# untitled.net
KiCad netlist of a schematic drawn in EAGLE
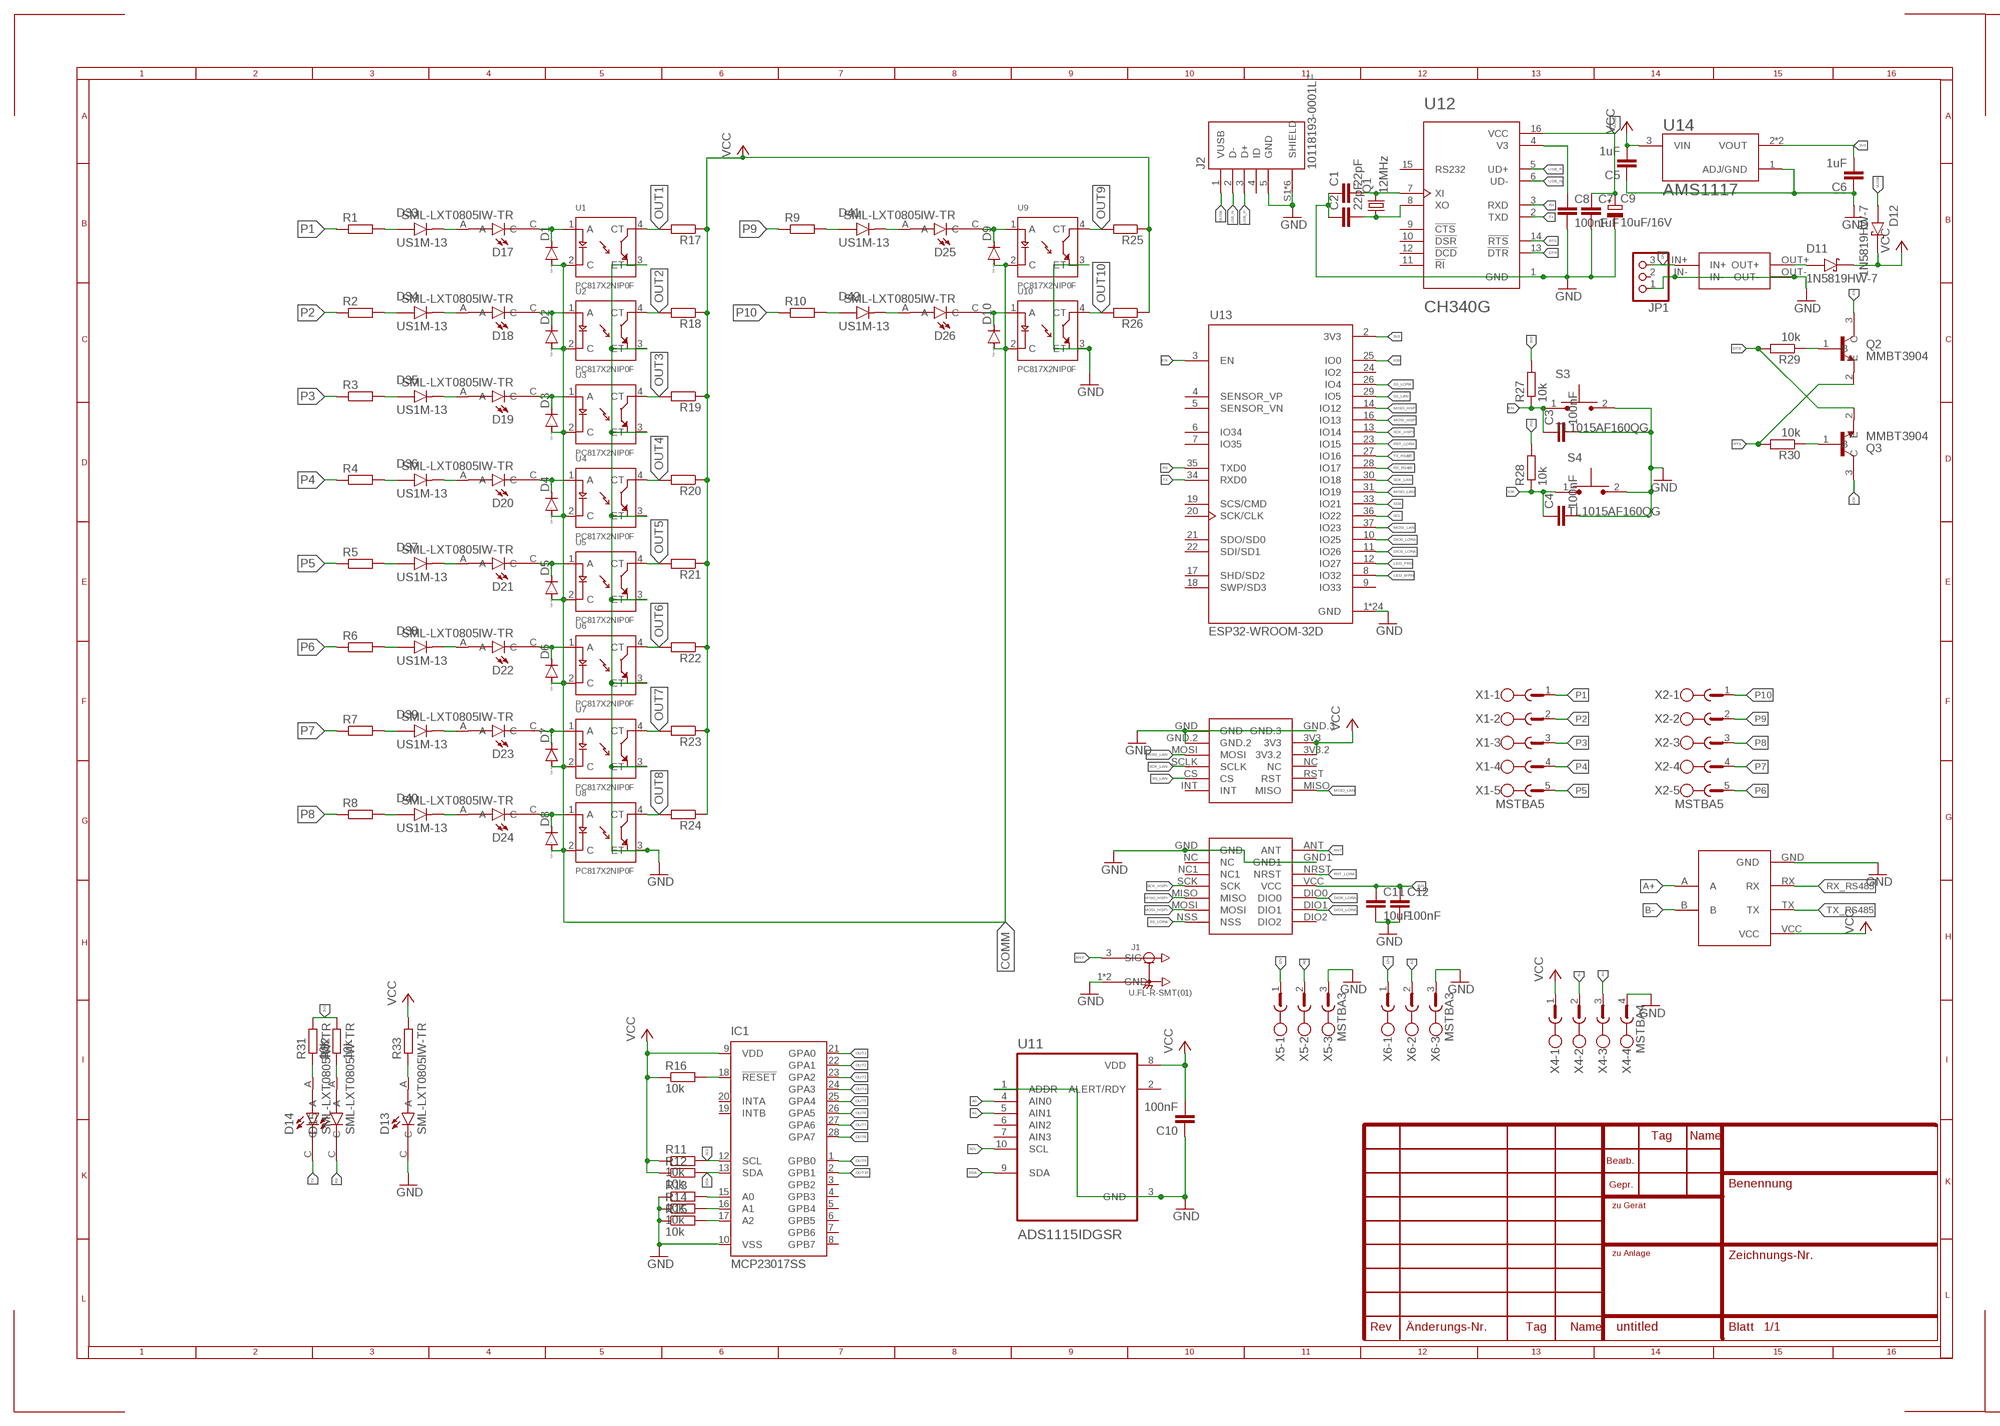
[diagram p0: schematic, sheet 1, part 1 of 2]
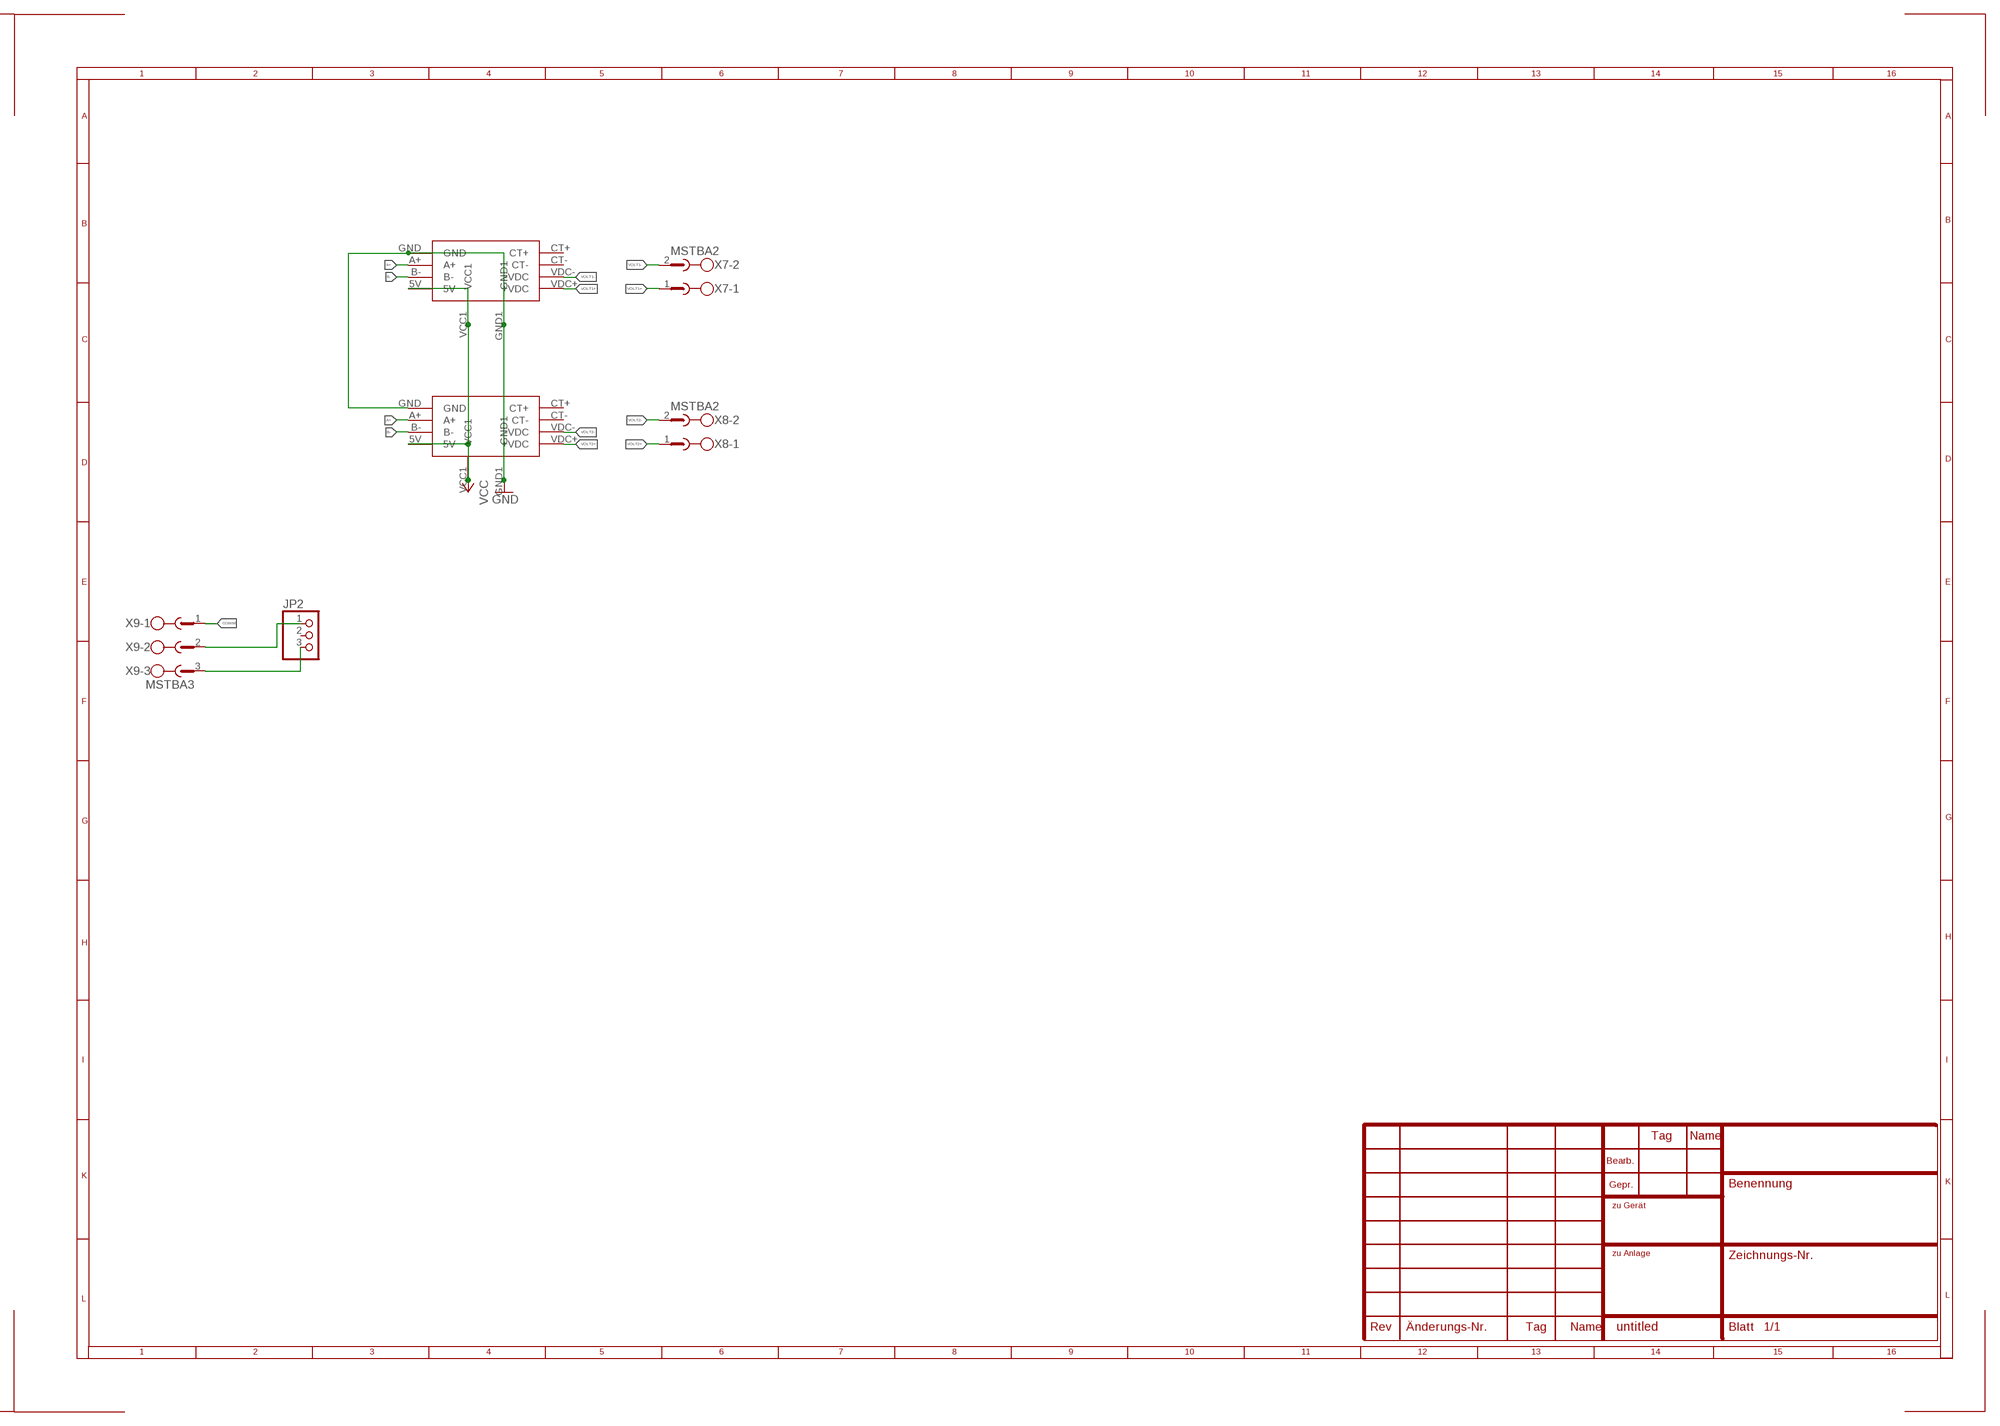
[diagram p1: schematic, sheet 1, part 2 of 2]

(export (version "E")
  (design (tool "Eeschema 10.0.6"))
  (components
    (comp (ref "C1")
      (value "22pF")
      (footprint "eagle-import:C0805K")
      (libsource (lib "eagle-import") (part "C-EUC0805K"))
    )
    (comp (ref "C2")
      (value "22pF")
      (footprint "eagle-import:C0805K")
      (libsource (lib "eagle-import") (part "C-EUC0805K"))
    )
    (comp (ref "C3")
      (value "100nF")
      (footprint "eagle-import:C0805K")
      (libsource (lib "eagle-import") (part "C-EUC0805K"))
    )
    (comp (ref "C4")
      (value "100nF")
      (footprint "eagle-import:C0805K")
      (libsource (lib "eagle-import") (part "C-EUC0805K"))
    )
    (comp (ref "C5")
      (value "1uF")
      (footprint "eagle-import:C0805K")
      (libsource (lib "eagle-import") (part "C-EUC0805K"))
    )
    (comp (ref "C6")
      (value "1uF")
      (footprint "eagle-import:C0805K")
      (libsource (lib "eagle-import") (part "C-EUC0805K"))
    )
    (comp (ref "C7")
      (value "1uF")
      (footprint "eagle-import:C0805K")
      (libsource (lib "eagle-import") (part "C-EUC0805K"))
    )
    (comp (ref "C8")
      (value "100nF")
      (footprint "eagle-import:C0805K")
      (libsource (lib "eagle-import") (part "C-EUC0805K"))
    )
    (comp (ref "C9")
      (value "10uF/16V")
      (footprint "eagle-import:153CLV-0505")
      (libsource (lib "eagle-import") (part "CPOL-EU153CLV-0505"))
    )
    (comp (ref "C10")
      (value "100nF")
      (footprint "eagle-import:C0805K")
      (libsource (lib "eagle-import") (part "C-EUC0805K"))
    )
    (comp (ref "C11")
      (value "10uF")
      (footprint "eagle-import:C0805K")
      (libsource (lib "eagle-import") (part "C-EUC0805K"))
    )
    (comp (ref "C12")
      (value "100nF")
      (footprint "eagle-import:C0805K")
      (libsource (lib "eagle-import") (part "C-EUC0805K"))
    )
    (comp (ref "D1")
      (value "DIODE-SOD123")
      (footprint "eagle-import:SOD123")
      (libsource (lib "eagle-import") (part "DIODE-SOD123"))
    )
    (comp (ref "D2")
      (value "DIODE-SOD123")
      (footprint "eagle-import:SOD123")
      (libsource (lib "eagle-import") (part "DIODE-SOD123"))
    )
    (comp (ref "D3")
      (value "DIODE-SOD123")
      (footprint "eagle-import:SOD123")
      (libsource (lib "eagle-import") (part "DIODE-SOD123"))
    )
    (comp (ref "D4")
      (value "DIODE-SOD123")
      (footprint "eagle-import:SOD123")
      (libsource (lib "eagle-import") (part "DIODE-SOD123"))
    )
    (comp (ref "D5")
      (value "DIODE-SOD123")
      (footprint "eagle-import:SOD123")
      (libsource (lib "eagle-import") (part "DIODE-SOD123"))
    )
    (comp (ref "D6")
      (value "DIODE-SOD123")
      (footprint "eagle-import:SOD123")
      (libsource (lib "eagle-import") (part "DIODE-SOD123"))
    )
    (comp (ref "D7")
      (value "DIODE-SOD123")
      (footprint "eagle-import:SOD123")
      (libsource (lib "eagle-import") (part "DIODE-SOD123"))
    )
    (comp (ref "D8")
      (value "DIODE-SOD123")
      (footprint "eagle-import:SOD123")
      (libsource (lib "eagle-import") (part "DIODE-SOD123"))
    )
    (comp (ref "D9")
      (value "DIODE-SOD123")
      (footprint "eagle-import:SOD123")
      (libsource (lib "eagle-import") (part "DIODE-SOD123"))
    )
    (comp (ref "D10")
      (value "DIODE-SOD123")
      (footprint "eagle-import:SOD123")
      (libsource (lib "eagle-import") (part "DIODE-SOD123"))
    )
    (comp (ref "D11")
      (value "1N5819HW-7")
      (footprint "eagle-import:SOD3715X145N")
      (fields (field (name "MF") "Diodes Inc."))
      (libsource (lib "eagle-import") (part "1N5819HW-7"))
    )
    (comp (ref "D12")
      (value "1N5819HW-7")
      (footprint "eagle-import:SOD3715X145N")
      (fields (field (name "MF") "Diodes Inc."))
      (libsource (lib "eagle-import") (part "1N5819HW-7"))
    )
    (comp (ref "D13")
      (value "SML-LXT0805IW-TR")
      (footprint "eagle-import:LEDC2012X120N")
      (fields (field (name "MF") "Lumex Opto/Components"))
      (libsource (lib "eagle-import") (part "SML-LXT0805IW-TR"))
    )
    (comp (ref "D14")
      (value "SML-LXT0805IW-TR")
      (footprint "eagle-import:LEDC2012X120N")
      (fields (field (name "MF") "Lumex Opto/Components"))
      (libsource (lib "eagle-import") (part "SML-LXT0805IW-TR"))
    )
    (comp (ref "D15")
      (value "SML-LXT0805IW-TR")
      (footprint "eagle-import:LEDC2012X120N")
      (fields (field (name "MF") "Lumex Opto/Components"))
      (libsource (lib "eagle-import") (part "SML-LXT0805IW-TR"))
    )
    (comp (ref "D17")
      (value "SML-LXT0805IW-TR")
      (footprint "eagle-import:LEDC2012X120N")
      (fields (field (name "MF") "Lumex Opto/Components"))
      (libsource (lib "eagle-import") (part "SML-LXT0805IW-TR"))
    )
    (comp (ref "D18")
      (value "SML-LXT0805IW-TR")
      (footprint "eagle-import:LEDC2012X120N")
      (fields (field (name "MF") "Lumex Opto/Components"))
      (libsource (lib "eagle-import") (part "SML-LXT0805IW-TR"))
    )
    (comp (ref "D19")
      (value "SML-LXT0805IW-TR")
      (footprint "eagle-import:LEDC2012X120N")
      (fields (field (name "MF") "Lumex Opto/Components"))
      (libsource (lib "eagle-import") (part "SML-LXT0805IW-TR"))
    )
    (comp (ref "D20")
      (value "SML-LXT0805IW-TR")
      (footprint "eagle-import:LEDC2012X120N")
      (fields (field (name "MF") "Lumex Opto/Components"))
      (libsource (lib "eagle-import") (part "SML-LXT0805IW-TR"))
    )
    (comp (ref "D21")
      (value "SML-LXT0805IW-TR")
      (footprint "eagle-import:LEDC2012X120N")
      (fields (field (name "MF") "Lumex Opto/Components"))
      (libsource (lib "eagle-import") (part "SML-LXT0805IW-TR"))
    )
    (comp (ref "D22")
      (value "SML-LXT0805IW-TR")
      (footprint "eagle-import:LEDC2012X120N")
      (fields (field (name "MF") "Lumex Opto/Components"))
      (libsource (lib "eagle-import") (part "SML-LXT0805IW-TR"))
    )
    (comp (ref "D23")
      (value "SML-LXT0805IW-TR")
      (footprint "eagle-import:LEDC2012X120N")
      (fields (field (name "MF") "Lumex Opto/Components"))
      (libsource (lib "eagle-import") (part "SML-LXT0805IW-TR"))
    )
    (comp (ref "D24")
      (value "SML-LXT0805IW-TR")
      (footprint "eagle-import:LEDC2012X120N")
      (fields (field (name "MF") "Lumex Opto/Components"))
      (libsource (lib "eagle-import") (part "SML-LXT0805IW-TR"))
    )
    (comp (ref "D25")
      (value "SML-LXT0805IW-TR")
      (footprint "eagle-import:LEDC2012X120N")
      (fields (field (name "MF") "Lumex Opto/Components"))
      (libsource (lib "eagle-import") (part "SML-LXT0805IW-TR"))
    )
    (comp (ref "D26")
      (value "SML-LXT0805IW-TR")
      (footprint "eagle-import:LEDC2012X120N")
      (fields (field (name "MF") "Lumex Opto/Components"))
      (libsource (lib "eagle-import") (part "SML-LXT0805IW-TR"))
    )
    (comp (ref "D33")
      (value "US1M-13")
      (footprint "eagle-import:DIOM5226X240N")
      (fields (field (name "MF") "Diodes Incorporated"))
      (libsource (lib "eagle-import") (part "US1M-13"))
    )
    (comp (ref "D34")
      (value "US1M-13")
      (footprint "eagle-import:DIOM5226X240N")
      (fields (field (name "MF") "Diodes Incorporated"))
      (libsource (lib "eagle-import") (part "US1M-13"))
    )
    (comp (ref "D35")
      (value "US1M-13")
      (footprint "eagle-import:DIOM5226X240N")
      (fields (field (name "MF") "Diodes Incorporated"))
      (libsource (lib "eagle-import") (part "US1M-13"))
    )
    (comp (ref "D36")
      (value "US1M-13")
      (footprint "eagle-import:DIOM5226X240N")
      (fields (field (name "MF") "Diodes Incorporated"))
      (libsource (lib "eagle-import") (part "US1M-13"))
    )
    (comp (ref "D37")
      (value "US1M-13")
      (footprint "eagle-import:DIOM5226X240N")
      (fields (field (name "MF") "Diodes Incorporated"))
      (libsource (lib "eagle-import") (part "US1M-13"))
    )
    (comp (ref "D38")
      (value "US1M-13")
      (footprint "eagle-import:DIOM5226X240N")
      (fields (field (name "MF") "Diodes Incorporated"))
      (libsource (lib "eagle-import") (part "US1M-13"))
    )
    (comp (ref "D39")
      (value "US1M-13")
      (footprint "eagle-import:DIOM5226X240N")
      (fields (field (name "MF") "Diodes Incorporated"))
      (libsource (lib "eagle-import") (part "US1M-13"))
    )
    (comp (ref "D40")
      (value "US1M-13")
      (footprint "eagle-import:DIOM5226X240N")
      (fields (field (name "MF") "Diodes Incorporated"))
      (libsource (lib "eagle-import") (part "US1M-13"))
    )
    (comp (ref "D41")
      (value "US1M-13")
      (footprint "eagle-import:DIOM5226X240N")
      (fields (field (name "MF") "Diodes Incorporated"))
      (libsource (lib "eagle-import") (part "US1M-13"))
    )
    (comp (ref "D42")
      (value "US1M-13")
      (footprint "eagle-import:DIOM5226X240N")
      (fields (field (name "MF") "Diodes Incorporated"))
      (libsource (lib "eagle-import") (part "US1M-13"))
    )
    (comp (ref "IC1")
      (value "MCP23017SS")
      (footprint "eagle-import:SSOP28")
      (fields (field (name "MF") "MICROCHIP") (field (name "MPN") "MCP23017-E/SS"))
      (libsource (lib "eagle-import") (part "MCP23017SS"))
    )
    (comp (ref "J1")
      (value "U.FL-R-SMT(01)")
      (footprint "eagle-import:HRS_U.FL-R-SMT(01)")
      (fields (field (name "MF") "Hirose"))
      (libsource (lib "eagle-import") (part "U.FL-R-SMT(01)"))
    )
    (comp (ref "J2")
      (value "10118193-0001LF")
      (footprint "eagle-import:FCI_10118193-0001LF")
      (fields (field (name "MF") "FCI"))
      (libsource (lib "eagle-import") (part "10118193-0001LF"))
    )
    (comp (ref "JP1")
      (value "PINHD-1X3CB")
      (footprint "eagle-import:1X03-CLEANBIG")
      (libsource (lib "eagle-import") (part "PINHD-1X3CB"))
    )
    (comp (ref "JP2")
      (value "PINHD-1X3CB")
      (footprint "eagle-import:1X03-CLEANBIG")
      (libsource (lib "eagle-import") (part "PINHD-1X3CB"))
    )
    (comp (ref "LORA-NICERF-V1")
      (value "LORA-NICERF-V2")
      (footprint "eagle-import:LORA-NICERF-V2")
      (libsource (lib "eagle-import") (part "LORA-NICERF-V2"))
    )
    (comp (ref "MINI1")
      (value "MINI560")
      (footprint "eagle-import:MINI560")
      (libsource (lib "eagle-import") (part "MINI560"))
    )
    (comp (ref "PZEM-DC1")
      (value "PZEM-DC")
      (footprint "eagle-import:PZEM-DC")
      (libsource (lib "eagle-import") (part "PZEM-DC"))
    )
    (comp (ref "PZEM-DC2")
      (value "PZEM-DC")
      (footprint "eagle-import:PZEM-DC")
      (libsource (lib "eagle-import") (part "PZEM-DC"))
    )
    (comp (ref "Q1")
      (value "12MHz")
      (footprint "eagle-import:SM49")
      (libsource (lib "eagle-import") (part "CRYSTALSM49"))
    )
    (comp (ref "Q2")
      (value "MMBT3904")
      (footprint "eagle-import:SOT95P240X120-3N")
      (fields (field (name "MF") "ON Semiconductor"))
      (libsource (lib "eagle-import") (part "MMBT3904"))
    )
    (comp (ref "Q3")
      (value "MMBT3904")
      (footprint "eagle-import:SOT95P240X120-3N")
      (fields (field (name "MF") "ON Semiconductor"))
      (libsource (lib "eagle-import") (part "MMBT3904"))
    )
    (comp (ref "R1")
      (value "R-EU_0414/15")
      (footprint "eagle-import:0414_15")
      (libsource (lib "eagle-import") (part "R-EU_0414/15"))
    )
    (comp (ref "R2")
      (value "R-EU_0414/15")
      (footprint "eagle-import:0414_15")
      (libsource (lib "eagle-import") (part "R-EU_0414/15"))
    )
    (comp (ref "R3")
      (value "R-EU_0414/15")
      (footprint "eagle-import:0414_15")
      (libsource (lib "eagle-import") (part "R-EU_0414/15"))
    )
    (comp (ref "R4")
      (value "R-EU_0414/15")
      (footprint "eagle-import:0414_15")
      (libsource (lib "eagle-import") (part "R-EU_0414/15"))
    )
    (comp (ref "R5")
      (value "R-EU_0414/15")
      (footprint "eagle-import:0414_15")
      (libsource (lib "eagle-import") (part "R-EU_0414/15"))
    )
    (comp (ref "R6")
      (value "R-EU_0414/15")
      (footprint "eagle-import:0414_15")
      (libsource (lib "eagle-import") (part "R-EU_0414/15"))
    )
    (comp (ref "R7")
      (value "R-EU_0414/15")
      (footprint "eagle-import:0414_15")
      (libsource (lib "eagle-import") (part "R-EU_0414/15"))
    )
    (comp (ref "R8")
      (value "R-EU_0414/15")
      (footprint "eagle-import:0414_15")
      (libsource (lib "eagle-import") (part "R-EU_0414/15"))
    )
    (comp (ref "R9")
      (value "R-EU_0414/15")
      (footprint "eagle-import:0414_15")
      (libsource (lib "eagle-import") (part "R-EU_0414/15"))
    )
    (comp (ref "R10")
      (value "R-EU_0414/15")
      (footprint "eagle-import:0414_15")
      (libsource (lib "eagle-import") (part "R-EU_0414/15"))
    )
    (comp (ref "R11")
      (value "10k")
      (footprint "eagle-import:R0805")
      (libsource (lib "eagle-import") (part "R-EU_R0805"))
    )
    (comp (ref "R12")
      (value "10k")
      (footprint "eagle-import:R0805")
      (libsource (lib "eagle-import") (part "R-EU_R0805"))
    )
    (comp (ref "R13")
      (value "10k")
      (footprint "eagle-import:R0805")
      (libsource (lib "eagle-import") (part "R-EU_R0805"))
    )
    (comp (ref "R14")
      (value "10k")
      (footprint "eagle-import:R0805")
      (libsource (lib "eagle-import") (part "R-EU_R0805"))
    )
    (comp (ref "R15")
      (value "10k")
      (footprint "eagle-import:R0805")
      (libsource (lib "eagle-import") (part "R-EU_R0805"))
    )
    (comp (ref "R16")
      (value "10k")
      (footprint "eagle-import:R0805")
      (libsource (lib "eagle-import") (part "R-EU_R0805"))
    )
    (comp (ref "R17")
      (value "R-EU_R0805")
      (footprint "eagle-import:R0805")
      (libsource (lib "eagle-import") (part "R-EU_R0805"))
    )
    (comp (ref "R18")
      (value "R-EU_R0805")
      (footprint "eagle-import:R0805")
      (libsource (lib "eagle-import") (part "R-EU_R0805"))
    )
    (comp (ref "R19")
      (value "R-EU_R0805")
      (footprint "eagle-import:R0805")
      (libsource (lib "eagle-import") (part "R-EU_R0805"))
    )
    (comp (ref "R20")
      (value "R-EU_R0805")
      (footprint "eagle-import:R0805")
      (libsource (lib "eagle-import") (part "R-EU_R0805"))
    )
    (comp (ref "R21")
      (value "R-EU_R0805")
      (footprint "eagle-import:R0805")
      (libsource (lib "eagle-import") (part "R-EU_R0805"))
    )
    (comp (ref "R22")
      (value "R-EU_R0805")
      (footprint "eagle-import:R0805")
      (libsource (lib "eagle-import") (part "R-EU_R0805"))
    )
    (comp (ref "R23")
      (value "R-EU_R0805")
      (footprint "eagle-import:R0805")
      (libsource (lib "eagle-import") (part "R-EU_R0805"))
    )
    (comp (ref "R24")
      (value "R-EU_R0805")
      (footprint "eagle-import:R0805")
      (libsource (lib "eagle-import") (part "R-EU_R0805"))
    )
    (comp (ref "R25")
      (value "R-EU_R0805")
      (footprint "eagle-import:R0805")
      (libsource (lib "eagle-import") (part "R-EU_R0805"))
    )
    (comp (ref "R26")
      (value "R-EU_R0805")
      (footprint "eagle-import:R0805")
      (libsource (lib "eagle-import") (part "R-EU_R0805"))
    )
    (comp (ref "R27")
      (value "10k")
      (footprint "eagle-import:R0805")
      (libsource (lib "eagle-import") (part "R-EU_R0805"))
    )
    (comp (ref "R28")
      (value "10k")
      (footprint "eagle-import:R0805")
      (libsource (lib "eagle-import") (part "R-EU_R0805"))
    )
    (comp (ref "R29")
      (value "10k")
      (footprint "eagle-import:R0805")
      (libsource (lib "eagle-import") (part "R-EU_R0805"))
    )
    (comp (ref "R30")
      (value "10k")
      (footprint "eagle-import:R0805")
      (libsource (lib "eagle-import") (part "R-EU_R0805"))
    )
    (comp (ref "R31")
      (value "10k")
      (footprint "eagle-import:R0805")
      (libsource (lib "eagle-import") (part "R-EU_R0805"))
    )
    (comp (ref "R32")
      (value "10k")
      (footprint "eagle-import:R0805")
      (libsource (lib "eagle-import") (part "R-EU_R0805"))
    )
    (comp (ref "R33")
      (value "330")
      (footprint "eagle-import:R0805")
      (libsource (lib "eagle-import") (part "R-EU_R0805"))
    )
    (comp (ref "S3")
      (value "TL1015AF160QG")
      (footprint "eagle-import:SW_TL1015AF160QG")
      (fields (field (name "MF") "E-Switch"))
      (libsource (lib "eagle-import") (part "TL1015AF160QG"))
    )
    (comp (ref "S4")
      (value "TL1015AF160QG")
      (footprint "eagle-import:SW_TL1015AF160QG")
      (fields (field (name "MF") "E-Switch"))
      (libsource (lib "eagle-import") (part "TL1015AF160QG"))
    )
    (comp (ref "TTL-RS1")
      (value "TTL-RS485")
      (footprint "eagle-import:TTL-RS485")
      (libsource (lib "eagle-import") (part "TTL-RS485"))
    )
    (comp (ref "U$1")
      (value "MINI_W5500")
      (footprint "eagle-import:MINI_W5500")
      (libsource (lib "eagle-import") (part "MINI_W5500"))
    )
    (comp (ref "U1")
      (value "PC817X2NIP0F")
      (footprint "eagle-import:SOT254P975X400-4N")
      (fields (field (name "MF") "Sharp Microelectronics"))
      (libsource (lib "eagle-import") (part "PC817X2NIP0F"))
    )
    (comp (ref "U2")
      (value "PC817X2NIP0F")
      (footprint "eagle-import:SOT254P975X400-4N")
      (fields (field (name "MF") "Sharp Microelectronics"))
      (libsource (lib "eagle-import") (part "PC817X2NIP0F"))
    )
    (comp (ref "U3")
      (value "PC817X2NIP0F")
      (footprint "eagle-import:SOT254P975X400-4N")
      (fields (field (name "MF") "Sharp Microelectronics"))
      (libsource (lib "eagle-import") (part "PC817X2NIP0F"))
    )
    (comp (ref "U4")
      (value "PC817X2NIP0F")
      (footprint "eagle-import:SOT254P975X400-4N")
      (fields (field (name "MF") "Sharp Microelectronics"))
      (libsource (lib "eagle-import") (part "PC817X2NIP0F"))
    )
    (comp (ref "U5")
      (value "PC817X2NIP0F")
      (footprint "eagle-import:SOT254P975X400-4N")
      (fields (field (name "MF") "Sharp Microelectronics"))
      (libsource (lib "eagle-import") (part "PC817X2NIP0F"))
    )
    (comp (ref "U6")
      (value "PC817X2NIP0F")
      (footprint "eagle-import:SOT254P975X400-4N")
      (fields (field (name "MF") "Sharp Microelectronics"))
      (libsource (lib "eagle-import") (part "PC817X2NIP0F"))
    )
    (comp (ref "U7")
      (value "PC817X2NIP0F")
      (footprint "eagle-import:SOT254P975X400-4N")
      (fields (field (name "MF") "Sharp Microelectronics"))
      (libsource (lib "eagle-import") (part "PC817X2NIP0F"))
    )
    (comp (ref "U8")
      (value "PC817X2NIP0F")
      (footprint "eagle-import:SOT254P975X400-4N")
      (fields (field (name "MF") "Sharp Microelectronics"))
      (libsource (lib "eagle-import") (part "PC817X2NIP0F"))
    )
    (comp (ref "U9")
      (value "PC817X2NIP0F")
      (footprint "eagle-import:SOT254P975X400-4N")
      (fields (field (name "MF") "Sharp Microelectronics"))
      (libsource (lib "eagle-import") (part "PC817X2NIP0F"))
    )
    (comp (ref "U10")
      (value "PC817X2NIP0F")
      (footprint "eagle-import:SOT254P975X400-4N")
      (fields (field (name "MF") "Sharp Microelectronics"))
      (libsource (lib "eagle-import") (part "PC817X2NIP0F"))
    )
    (comp (ref "U11")
      (value "ADS1115IDGSR")
      (footprint "eagle-import:SOP50P490X110-10N")
      (fields (field (name "MF") "Texas Instruments"))
      (libsource (lib "eagle-import") (part "ADS1115IDGSR"))
    )
    (comp (ref "U12")
      (value "CH340G")
      (footprint "eagle-import:SOIC127P600X180-16N")
      (fields (field (name "MF") "WCH") (field (name "MP") "Ch340G"))
      (libsource (lib "eagle-import") (part "CH340G"))
    )
    (comp (ref "U13")
      (value "ESP32-WROOM-32D")
      (footprint "eagle-import:MODULE_ESP32-WROOM-32D")
      (fields (field (name "MF") "Espressif Systems"))
      (libsource (lib "eagle-import") (part "ESP32-WROOM-32D"))
    )
    (comp (ref "U14")
      (value "AMS1117")
      (footprint "eagle-import:SOT229P700X180-4N")
      (fields (field (name "MF") "Advanced Monolithic Systems"))
      (libsource (lib "eagle-import") (part "AMS1117"))
    )
    (comp (ref "X1")
      (value "MSTBA5")
      (footprint "eagle-import:MSTBA5")
      (fields (field (name "MPN") "1757271"))
      (libsource (lib "eagle-import") (part "MSTBA5"))
    )
    (comp (ref "X2")
      (value "MSTBA5")
      (footprint "eagle-import:MSTBA5")
      (fields (field (name "MPN") "1757271"))
      (libsource (lib "eagle-import") (part "MSTBA5"))
    )
    (comp (ref "X4")
      (value "MSTBA4")
      (footprint "eagle-import:MSTBA4")
      (fields (field (name "MF") "FARNELL") (field (name "MPN") "1757268"))
      (libsource (lib "eagle-import") (part "MSTBA4"))
    )
    (comp (ref "X5")
      (value "MSTBA3")
      (footprint "eagle-import:MSTBA3")
      (fields (field (name "MF") "FARNELL") (field (name "MPN") "1757255"))
      (libsource (lib "eagle-import") (part "MSTBA3"))
    )
    (comp (ref "X6")
      (value "MSTBA3")
      (footprint "eagle-import:MSTBA3")
      (fields (field (name "MF") "FARNELL") (field (name "MPN") "1757255"))
      (libsource (lib "eagle-import") (part "MSTBA3"))
    )
    (comp (ref "X7")
      (value "MSTBA2")
      (footprint "eagle-import:MSTBA2")
      (fields (field (name "MF") "FARNELL") (field (name "MPN") "1757242"))
      (libsource (lib "eagle-import") (part "MSTBA2"))
    )
    (comp (ref "X8")
      (value "MSTBA2")
      (footprint "eagle-import:MSTBA2")
      (fields (field (name "MF") "FARNELL") (field (name "MPN") "1757242"))
      (libsource (lib "eagle-import") (part "MSTBA2"))
    )
    (comp (ref "X9")
      (value "MSTBA3")
      (footprint "eagle-import:MSTBA3")
      (fields (field (name "MF") "FARNELL") (field (name "MPN") "1757255"))
      (libsource (lib "eagle-import") (part "MSTBA3"))
    )
  )
  (nets
    (net (code "1") (name "3V3") (class "Default")
      (node (ref "C11") (pin "1") (pinfunction "1_1") (pintype "passive"))
      (node (ref "C12") (pin "1") (pinfunction "1_1") (pintype "passive"))
      (node (ref "C6") (pin "2") (pinfunction "2_2") (pintype "passive"))
      (node (ref "LORA-NICERF-V1") (pin "VCC") (pinfunction "VCC_VCC") (pintype "bidirectional"))
      (node (ref "R27") (pin "2") (pinfunction "2_2") (pintype "passive"))
      (node (ref "R28") (pin "2") (pinfunction "2_2") (pintype "passive"))
      (node (ref "R31") (pin "2") (pinfunction "2_2") (pintype "passive"))
      (node (ref "R32") (pin "2") (pinfunction "2_2") (pintype "passive"))
      (node (ref "U13") (pin "2") (pinfunction "3V3_2") (pintype "power_in"))
      (node (ref "U14") (pin "2") (pinfunction "VOUT_2") (pintype "output"))
      (node (ref "U14") (pin "4") (pinfunction "VOUT_4") (pintype "output"))
    )
    (net (code "2") (name "12V") (class "Default")
      (node (ref "JP1") (pin "3") (pinfunction "3_3") (pintype "passive"))
      (node (ref "MINI1") (pin "IN+") (pinfunction "IN+_IN+") (pintype "bidirectional"))
      (node (ref "X5") (pin "1") (pinfunction "1_1") (pintype "passive"))
      (node (ref "X6") (pin "1") (pinfunction "1_1") (pintype "passive"))
    )
    (net (code "3") (name "A+") (class "Default")
      (node (ref "PZEM-DC1") (pin "A+") (pinfunction "A+_A+") (pintype "bidirectional"))
      (node (ref "PZEM-DC2") (pin "A+") (pinfunction "A+_A+") (pintype "bidirectional"))
      (node (ref "TTL-RS1") (pin "A") (pinfunction "A_A") (pintype "bidirectional"))
      (node (ref "X4") (pin "3") (pinfunction "1_3") (pintype "passive"))
    )
    (net (code "4") (name "A0") (class "Default")
      (node (ref "U11") (pin "4") (pinfunction "AIN0_4") (pintype "input"))
      (node (ref "X5") (pin "2") (pinfunction "1_2") (pintype "passive"))
    )
    (net (code "5") (name "A1") (class "Default")
      (node (ref "U11") (pin "5") (pinfunction "AIN1_5") (pintype "input"))
      (node (ref "X6") (pin "2") (pinfunction "1_2") (pintype "passive"))
    )
    (net (code "6") (name "ANT") (class "Default")
      (node (ref "J1") (pin "3") (pinfunction "SIG_3") (pintype "passive"))
      (node (ref "LORA-NICERF-V1") (pin "ANT") (pinfunction "ANT_ANT") (pintype "bidirectional"))
    )
    (net (code "7") (name "B-") (class "Default")
      (node (ref "PZEM-DC1") (pin "B-") (pinfunction "B-_B-") (pintype "bidirectional"))
      (node (ref "PZEM-DC2") (pin "B-") (pinfunction "B-_B-") (pintype "bidirectional"))
      (node (ref "TTL-RS1") (pin "B") (pinfunction "B_B") (pintype "bidirectional"))
      (node (ref "X4") (pin "2") (pinfunction "1_2") (pintype "passive"))
    )
    (net (code "8") (name "COMM") (class "Default")
      (node (ref "D1") (pin "A") (pinfunction "A_A") (pintype "passive"))
      (node (ref "D10") (pin "A") (pinfunction "A_A") (pintype "passive"))
      (node (ref "D2") (pin "A") (pinfunction "A_A") (pintype "passive"))
      (node (ref "D3") (pin "A") (pinfunction "A_A") (pintype "passive"))
      (node (ref "D4") (pin "A") (pinfunction "A_A") (pintype "passive"))
      (node (ref "D5") (pin "A") (pinfunction "A_A") (pintype "passive"))
      (node (ref "D6") (pin "A") (pinfunction "A_A") (pintype "passive"))
      (node (ref "D7") (pin "A") (pinfunction "A_A") (pintype "passive"))
      (node (ref "D8") (pin "A") (pinfunction "A_A") (pintype "passive"))
      (node (ref "D9") (pin "A") (pinfunction "A_A") (pintype "passive"))
      (node (ref "U1") (pin "2") (pinfunction "C_2") (pintype "passive"))
      (node (ref "U10") (pin "2") (pinfunction "C_2") (pintype "passive"))
      (node (ref "U2") (pin "2") (pinfunction "C_2") (pintype "passive"))
      (node (ref "U3") (pin "2") (pinfunction "C_2") (pintype "passive"))
      (node (ref "U4") (pin "2") (pinfunction "C_2") (pintype "passive"))
      (node (ref "U5") (pin "2") (pinfunction "C_2") (pintype "passive"))
      (node (ref "U6") (pin "2") (pinfunction "C_2") (pintype "passive"))
      (node (ref "U7") (pin "2") (pinfunction "C_2") (pintype "passive"))
      (node (ref "U8") (pin "2") (pinfunction "C_2") (pintype "passive"))
      (node (ref "U9") (pin "2") (pinfunction "C_2") (pintype "passive"))
      (node (ref "X9") (pin "1") (pinfunction "1_1") (pintype "passive"))
    )
    (net (code "9") (name "DIO0_LORA") (class "Default")
      (node (ref "LORA-NICERF-V1") (pin "DIO0") (pinfunction "DIO0_DIO0") (pintype "bidirectional"))
      (node (ref "U13") (pin "10") (pinfunction "IO25_10") (pintype "bidirectional"))
    )
    (net (code "10") (name "DIO1_LORA") (class "Default")
      (node (ref "LORA-NICERF-V1") (pin "DIO1") (pinfunction "DIO1_DIO1") (pintype "bidirectional"))
      (node (ref "U13") (pin "11") (pinfunction "IO26_11") (pintype "bidirectional"))
    )
    (net (code "11") (name "DTR") (class "Default")
      (node (ref "Q3") (pin "2") (pinfunction "E_2") (pintype "passive"))
      (node (ref "R29") (pin "2") (pinfunction "2_2") (pintype "passive"))
      (node (ref "U12") (pin "13") (pinfunction "~{DTR}_13") (pintype "output"))
    )
    (net (code "12") (name "EN") (class "Default")
      (node (ref "C3") (pin "1") (pinfunction "1_1") (pintype "passive"))
      (node (ref "Q2") (pin "3") (pinfunction "C_3") (pintype "passive"))
      (node (ref "R27") (pin "1") (pinfunction "1_1") (pintype "passive"))
      (node (ref "S3") (pin "1") (pinfunction "1_1") (pintype "passive"))
      (node (ref "U13") (pin "3") (pinfunction "EN_3") (pintype "input"))
    )
    (net (code "13") (name "GND") (class "Default")
      (node (ref "C1") (pin "1") (pinfunction "1_1") (pintype "passive"))
      (node (ref "C10") (pin "1") (pinfunction "1_1") (pintype "passive"))
      (node (ref "C11") (pin "2") (pinfunction "2_2") (pintype "passive"))
      (node (ref "C12") (pin "2") (pinfunction "2_2") (pintype "passive"))
      (node (ref "C2") (pin "1") (pinfunction "1_1") (pintype "passive"))
      (node (ref "C3") (pin "2") (pinfunction "2_2") (pintype "passive"))
      (node (ref "C4") (pin "2") (pinfunction "2_2") (pintype "passive"))
      (node (ref "C5") (pin "1") (pinfunction "1_1") (pintype "passive"))
      (node (ref "C6") (pin "1") (pinfunction "1_1") (pintype "passive"))
      (node (ref "C7") (pin "2") (pinfunction "2_2") (pintype "passive"))
      (node (ref "C8") (pin "2") (pinfunction "2_2") (pintype "passive"))
      (node (ref "C9") (pin "-") (pinfunction "-_-") (pintype "passive"))
      (node (ref "D13") (pin "C") (pinfunction "C_C") (pintype "passive"))
      (node (ref "IC1") (pin "10") (pinfunction "VSS_10") (pintype "power_in"))
      (node (ref "J1") (pin "1") (pinfunction "GND_1") (pintype "passive"))
      (node (ref "J1") (pin "2") (pinfunction "GND_2") (pintype "passive"))
      (node (ref "J2") (pin "5") (pinfunction "GND_5") (pintype "passive"))
      (node (ref "J2") (pin "S1") (pinfunction "SHIELD_S1") (pintype "passive"))
      (node (ref "J2") (pin "S2") (pinfunction "SHIELD_S2") (pintype "passive"))
      (node (ref "J2") (pin "S3") (pinfunction "SHIELD_S3") (pintype "passive"))
      (node (ref "J2") (pin "S4") (pinfunction "SHIELD_S4") (pintype "passive"))
      (node (ref "J2") (pin "S5") (pinfunction "SHIELD_S5") (pintype "passive"))
      (node (ref "J2") (pin "S6") (pinfunction "SHIELD_S6") (pintype "passive"))
      (node (ref "JP1") (pin "1") (pinfunction "1_1") (pintype "passive"))
      (node (ref "LORA-NICERF-V1") (pin "GND") (pinfunction "GND_GND") (pintype "bidirectional"))
      (node (ref "LORA-NICERF-V1") (pin "GND1") (pinfunction "GND1_GND1") (pintype "bidirectional"))
      (node (ref "MINI1") (pin "IN-") (pinfunction "IN-_IN-") (pintype "bidirectional"))
      (node (ref "MINI1") (pin "OUT-") (pinfunction "OUT-_OUT-") (pintype "bidirectional"))
      (node (ref "PZEM-DC1") (pin "GND") (pinfunction "GND_GND") (pintype "bidirectional"))
      (node (ref "PZEM-DC1") (pin "GND1") (pinfunction "GND1_GND1") (pintype "bidirectional"))
      (node (ref "PZEM-DC2") (pin "GND") (pinfunction "GND_GND") (pintype "bidirectional"))
      (node (ref "PZEM-DC2") (pin "GND1") (pinfunction "GND1_GND1") (pintype "bidirectional"))
      (node (ref "R13") (pin "1") (pinfunction "1_1") (pintype "passive"))
      (node (ref "R14") (pin "1") (pinfunction "1_1") (pintype "passive"))
      (node (ref "R15") (pin "1") (pinfunction "1_1") (pintype "passive"))
      (node (ref "S3") (pin "2") (pinfunction "2_2") (pintype "passive"))
      (node (ref "S4") (pin "2") (pinfunction "2_2") (pintype "passive"))
      (node (ref "TTL-RS1") (pin "GND") (pinfunction "GND_GND") (pintype "bidirectional"))
      (node (ref "U$1") (pin "GND") (pinfunction "GND_GND") (pintype "bidirectional"))
      (node (ref "U$1") (pin "GND.2") (pinfunction "GND.2_GND.2") (pintype "bidirectional"))
      (node (ref "U$1") (pin "GND.3") (pinfunction "GND.3_GND.3") (pintype "bidirectional"))
      (node (ref "U1") (pin "3") (pinfunction "ET_3") (pintype "passive"))
      (node (ref "U10") (pin "3") (pinfunction "ET_3") (pintype "passive"))
      (node (ref "U11") (pin "1") (pinfunction "ADDR_1") (pintype "input"))
      (node (ref "U11") (pin "3") (pinfunction "GND_3") (pintype "power_in"))
      (node (ref "U12") (pin "1") (pinfunction "GND_1") (pintype "power_in"))
      (node (ref "U13") (pin "1") (pinfunction "GND_1") (pintype "power_in"))
      (node (ref "U13") (pin "15") (pinfunction "GND_15") (pintype "power_in"))
      (node (ref "U13") (pin "38") (pinfunction "GND_38") (pintype "power_in"))
      (node (ref "U13") (pin "39_1") (pinfunction "GND_39_1") (pintype "power_in"))
      (node (ref "U13") (pin "39_10") (pinfunction "GND_39_10") (pintype "power_in"))
      (node (ref "U13") (pin "39_11") (pinfunction "GND_39_11") (pintype "power_in"))
      (node (ref "U13") (pin "39_12") (pinfunction "GND_39_12") (pintype "power_in"))
      (node (ref "U13") (pin "39_13") (pinfunction "GND_39_13") (pintype "power_in"))
      (node (ref "U13") (pin "39_14") (pinfunction "GND_39_14") (pintype "power_in"))
      (node (ref "U13") (pin "39_15") (pinfunction "GND_39_15") (pintype "power_in"))
      (node (ref "U13") (pin "39_16") (pinfunction "GND_39_16") (pintype "power_in"))
      (node (ref "U13") (pin "39_17") (pinfunction "GND_39_17") (pintype "power_in"))
      (node (ref "U13") (pin "39_18") (pinfunction "GND_39_18") (pintype "power_in"))
      (node (ref "U13") (pin "39_19") (pinfunction "GND_39_19") (pintype "power_in"))
      (node (ref "U13") (pin "39_2") (pinfunction "GND_39_2") (pintype "power_in"))
      (node (ref "U13") (pin "39_20") (pinfunction "GND_39_20") (pintype "power_in"))
      (node (ref "U13") (pin "39_21") (pinfunction "GND_39_21") (pintype "power_in"))
      (node (ref "U13") (pin "39_3") (pinfunction "GND_39_3") (pintype "power_in"))
      (node (ref "U13") (pin "39_4") (pinfunction "GND_39_4") (pintype "power_in"))
      (node (ref "U13") (pin "39_5") (pinfunction "GND_39_5") (pintype "power_in"))
      (node (ref "U13") (pin "39_6") (pinfunction "GND_39_6") (pintype "power_in"))
      (node (ref "U13") (pin "39_7") (pinfunction "GND_39_7") (pintype "power_in"))
      (node (ref "U13") (pin "39_8") (pinfunction "GND_39_8") (pintype "power_in"))
      (node (ref "U13") (pin "39_9") (pinfunction "GND_39_9") (pintype "power_in"))
      (node (ref "U14") (pin "1") (pinfunction "ADJ/GND_1") (pintype "power_in"))
      (node (ref "U2") (pin "3") (pinfunction "ET_3") (pintype "passive"))
      (node (ref "U3") (pin "3") (pinfunction "ET_3") (pintype "passive"))
      (node (ref "U4") (pin "3") (pinfunction "ET_3") (pintype "passive"))
      (node (ref "U5") (pin "3") (pinfunction "ET_3") (pintype "passive"))
      (node (ref "U6") (pin "3") (pinfunction "ET_3") (pintype "passive"))
      (node (ref "U7") (pin "3") (pinfunction "ET_3") (pintype "passive"))
      (node (ref "U8") (pin "3") (pinfunction "ET_3") (pintype "passive"))
      (node (ref "U9") (pin "3") (pinfunction "ET_3") (pintype "passive"))
      (node (ref "X4") (pin "4") (pinfunction "1_4") (pintype "passive"))
      (node (ref "X5") (pin "3") (pinfunction "1_3") (pintype "passive"))
      (node (ref "X6") (pin "3") (pinfunction "1_3") (pintype "passive"))
    )
    (net (code "14") (name "IO0") (class "Default")
      (node (ref "C4") (pin "1") (pinfunction "1_1") (pintype "passive"))
      (node (ref "Q3") (pin "3") (pinfunction "C_3") (pintype "passive"))
      (node (ref "R28") (pin "1") (pinfunction "1_1") (pintype "passive"))
      (node (ref "S4") (pin "1") (pinfunction "1_1") (pintype "passive"))
      (node (ref "U13") (pin "25") (pinfunction "IO0_25") (pintype "bidirectional"))
    )
    (net (code "15") (name "LED_PRS") (class "Default")
      (node (ref "U13") (pin "12") (pinfunction "IO27_12") (pintype "bidirectional"))
    )
    (net (code "16") (name "LED_WRN") (class "Default")
      (node (ref "U13") (pin "8") (pinfunction "IO32_8") (pintype "bidirectional"))
    )
    (net (code "17") (name "MISO_HSPI") (class "Default")
      (node (ref "LORA-NICERF-V1") (pin "MISO") (pinfunction "MISO_MISO") (pintype "bidirectional"))
      (node (ref "U13") (pin "14") (pinfunction "IO12_14") (pintype "bidirectional"))
    )
    (net (code "18") (name "MISO_LAN") (class "Default")
      (node (ref "U$1") (pin "MISO") (pinfunction "MISO_MISO") (pintype "bidirectional"))
      (node (ref "U13") (pin "31") (pinfunction "IO19_31") (pintype "bidirectional"))
    )
    (net (code "19") (name "MOSI_HSPI") (class "Default")
      (node (ref "LORA-NICERF-V1") (pin "MOSI") (pinfunction "MOSI_MOSI") (pintype "bidirectional"))
      (node (ref "U13") (pin "16") (pinfunction "IO13_16") (pintype "bidirectional"))
    )
    (net (code "20") (name "MOSI_LAN") (class "Default")
      (node (ref "U$1") (pin "MOSI") (pinfunction "MOSI_MOSI") (pintype "bidirectional"))
      (node (ref "U13") (pin "37") (pinfunction "IO23_37") (pintype "bidirectional"))
    )
    (net (code "21") (name "Net-(D11-PadA)") (class "Default")
      (node (ref "D11") (pin "A") (pinfunction "A_A") (pintype "passive"))
      (node (ref "MINI1") (pin "OUT+") (pinfunction "OUT+_OUT+") (pintype "bidirectional"))
    )
    (net (code "22") (name "Net-(D13-PadA)") (class "Default")
      (node (ref "D13") (pin "A") (pinfunction "A_A") (pintype "passive"))
      (node (ref "R33") (pin "1") (pinfunction "1_1") (pintype "passive"))
    )
    (net (code "23") (name "Net-(D14-PadA)") (class "Default")
      (node (ref "D14") (pin "A") (pinfunction "A_A") (pintype "passive"))
      (node (ref "R31") (pin "1") (pinfunction "1_1") (pintype "passive"))
    )
    (net (code "24") (name "Net-(D15-PadA)") (class "Default")
      (node (ref "D15") (pin "A") (pinfunction "A_A") (pintype "passive"))
      (node (ref "R32") (pin "1") (pinfunction "1_1") (pintype "passive"))
    )
    (net (code "25") (name "Net-(D33-K)") (class "Default")
      (node (ref "D17") (pin "A") (pinfunction "A_A") (pintype "passive"))
      (node (ref "D33") (pin "C") (pinfunction "K_C") (pintype "passive"))
    )
    (net (code "26") (name "Net-(D33-PadA)") (class "Default")
      (node (ref "D33") (pin "A") (pinfunction "A_A") (pintype "passive"))
      (node (ref "R1") (pin "2") (pinfunction "2_2") (pintype "passive"))
    )
    (net (code "27") (name "Net-(D34-K)") (class "Default")
      (node (ref "D18") (pin "A") (pinfunction "A_A") (pintype "passive"))
      (node (ref "D34") (pin "C") (pinfunction "K_C") (pintype "passive"))
    )
    (net (code "28") (name "Net-(D34-PadA)") (class "Default")
      (node (ref "D34") (pin "A") (pinfunction "A_A") (pintype "passive"))
      (node (ref "R2") (pin "2") (pinfunction "2_2") (pintype "passive"))
    )
    (net (code "29") (name "Net-(D35-K)") (class "Default")
      (node (ref "D19") (pin "A") (pinfunction "A_A") (pintype "passive"))
      (node (ref "D35") (pin "C") (pinfunction "K_C") (pintype "passive"))
    )
    (net (code "30") (name "Net-(D35-PadA)") (class "Default")
      (node (ref "D35") (pin "A") (pinfunction "A_A") (pintype "passive"))
      (node (ref "R3") (pin "2") (pinfunction "2_2") (pintype "passive"))
    )
    (net (code "31") (name "Net-(D36-K)") (class "Default")
      (node (ref "D20") (pin "A") (pinfunction "A_A") (pintype "passive"))
      (node (ref "D36") (pin "C") (pinfunction "K_C") (pintype "passive"))
    )
    (net (code "32") (name "Net-(D36-PadA)") (class "Default")
      (node (ref "D36") (pin "A") (pinfunction "A_A") (pintype "passive"))
      (node (ref "R4") (pin "2") (pinfunction "2_2") (pintype "passive"))
    )
    (net (code "33") (name "Net-(D37-K)") (class "Default")
      (node (ref "D21") (pin "A") (pinfunction "A_A") (pintype "passive"))
      (node (ref "D37") (pin "C") (pinfunction "K_C") (pintype "passive"))
    )
    (net (code "34") (name "Net-(D37-PadA)") (class "Default")
      (node (ref "D37") (pin "A") (pinfunction "A_A") (pintype "passive"))
      (node (ref "R5") (pin "2") (pinfunction "2_2") (pintype "passive"))
    )
    (net (code "35") (name "Net-(D38-K)") (class "Default")
      (node (ref "D22") (pin "A") (pinfunction "A_A") (pintype "passive"))
      (node (ref "D38") (pin "C") (pinfunction "K_C") (pintype "passive"))
    )
    (net (code "36") (name "Net-(D38-PadA)") (class "Default")
      (node (ref "D38") (pin "A") (pinfunction "A_A") (pintype "passive"))
      (node (ref "R6") (pin "2") (pinfunction "2_2") (pintype "passive"))
    )
    (net (code "37") (name "Net-(D39-K)") (class "Default")
      (node (ref "D23") (pin "A") (pinfunction "A_A") (pintype "passive"))
      (node (ref "D39") (pin "C") (pinfunction "K_C") (pintype "passive"))
    )
    (net (code "38") (name "Net-(D39-PadA)") (class "Default")
      (node (ref "D39") (pin "A") (pinfunction "A_A") (pintype "passive"))
      (node (ref "R7") (pin "2") (pinfunction "2_2") (pintype "passive"))
    )
    (net (code "39") (name "Net-(D40-K)") (class "Default")
      (node (ref "D24") (pin "A") (pinfunction "A_A") (pintype "passive"))
      (node (ref "D40") (pin "C") (pinfunction "K_C") (pintype "passive"))
    )
    (net (code "40") (name "Net-(D40-PadA)") (class "Default")
      (node (ref "D40") (pin "A") (pinfunction "A_A") (pintype "passive"))
      (node (ref "R8") (pin "2") (pinfunction "2_2") (pintype "passive"))
    )
    (net (code "41") (name "Net-(D41-K)") (class "Default")
      (node (ref "D25") (pin "A") (pinfunction "A_A") (pintype "passive"))
      (node (ref "D41") (pin "C") (pinfunction "K_C") (pintype "passive"))
    )
    (net (code "42") (name "Net-(D41-PadA)") (class "Default")
      (node (ref "D41") (pin "A") (pinfunction "A_A") (pintype "passive"))
      (node (ref "R9") (pin "2") (pinfunction "2_2") (pintype "passive"))
    )
    (net (code "43") (name "Net-(D42-K)") (class "Default")
      (node (ref "D26") (pin "A") (pinfunction "A_A") (pintype "passive"))
      (node (ref "D42") (pin "C") (pinfunction "K_C") (pintype "passive"))
    )
    (net (code "44") (name "Net-(D42-PadA)") (class "Default")
      (node (ref "D42") (pin "A") (pinfunction "A_A") (pintype "passive"))
      (node (ref "R10") (pin "2") (pinfunction "2_2") (pintype "passive"))
    )
    (net (code "45") (name "Net-(IC1-A0)") (class "Default")
      (node (ref "IC1") (pin "15") (pinfunction "A0_15") (pintype "input"))
      (node (ref "R13") (pin "2") (pinfunction "2_2") (pintype "passive"))
    )
    (net (code "46") (name "Net-(IC1-A1)") (class "Default")
      (node (ref "IC1") (pin "16") (pinfunction "A1_16") (pintype "input"))
      (node (ref "R14") (pin "2") (pinfunction "2_2") (pintype "passive"))
    )
    (net (code "47") (name "Net-(IC1-A2)") (class "Default")
      (node (ref "IC1") (pin "17") (pinfunction "A2_17") (pintype "input"))
      (node (ref "R15") (pin "2") (pinfunction "2_2") (pintype "passive"))
    )
    (net (code "48") (name "Net-(IC1-~{RESET})") (class "Default")
      (node (ref "IC1") (pin "18") (pinfunction "~{RESET}_18") (pintype "input"))
      (node (ref "R16") (pin "2") (pinfunction "2_2") (pintype "passive"))
    )
    (net (code "49") (name "Net-(Q2-B)") (class "Default")
      (node (ref "Q2") (pin "1") (pinfunction "B_1") (pintype "passive"))
      (node (ref "R29") (pin "1") (pinfunction "1_1") (pintype "passive"))
    )
    (net (code "50") (name "Net-(Q3-B)") (class "Default")
      (node (ref "Q3") (pin "1") (pinfunction "B_1") (pintype "passive"))
      (node (ref "R30") (pin "1") (pinfunction "1_1") (pintype "passive"))
    )
    (net (code "51") (name "Net-(U1-A)") (class "Default")
      (node (ref "D1") (pin "C") (pinfunction "C_C") (pintype "passive"))
      (node (ref "D17") (pin "C") (pinfunction "C_C") (pintype "passive"))
      (node (ref "U1") (pin "1") (pinfunction "A_1") (pintype "passive"))
    )
    (net (code "52") (name "Net-(U2-A)") (class "Default")
      (node (ref "D18") (pin "C") (pinfunction "C_C") (pintype "passive"))
      (node (ref "D2") (pin "C") (pinfunction "C_C") (pintype "passive"))
      (node (ref "U2") (pin "1") (pinfunction "A_1") (pintype "passive"))
    )
    (net (code "53") (name "Net-(U3-A)") (class "Default")
      (node (ref "D19") (pin "C") (pinfunction "C_C") (pintype "passive"))
      (node (ref "D3") (pin "C") (pinfunction "C_C") (pintype "passive"))
      (node (ref "U3") (pin "1") (pinfunction "A_1") (pintype "passive"))
    )
    (net (code "54") (name "Net-(U4-A)") (class "Default")
      (node (ref "D20") (pin "C") (pinfunction "C_C") (pintype "passive"))
      (node (ref "D4") (pin "C") (pinfunction "C_C") (pintype "passive"))
      (node (ref "U4") (pin "1") (pinfunction "A_1") (pintype "passive"))
    )
    (net (code "55") (name "Net-(U5-A)") (class "Default")
      (node (ref "D21") (pin "C") (pinfunction "C_C") (pintype "passive"))
      (node (ref "D5") (pin "C") (pinfunction "C_C") (pintype "passive"))
      (node (ref "U5") (pin "1") (pinfunction "A_1") (pintype "passive"))
    )
    (net (code "56") (name "Net-(U6-A)") (class "Default")
      (node (ref "D22") (pin "C") (pinfunction "C_C") (pintype "passive"))
      (node (ref "D6") (pin "C") (pinfunction "C_C") (pintype "passive"))
      (node (ref "U6") (pin "1") (pinfunction "A_1") (pintype "passive"))
    )
    (net (code "57") (name "Net-(U7-A)") (class "Default")
      (node (ref "D23") (pin "C") (pinfunction "C_C") (pintype "passive"))
      (node (ref "D7") (pin "C") (pinfunction "C_C") (pintype "passive"))
      (node (ref "U7") (pin "1") (pinfunction "A_1") (pintype "passive"))
    )
    (net (code "58") (name "Net-(U8-A)") (class "Default")
      (node (ref "D24") (pin "C") (pinfunction "C_C") (pintype "passive"))
      (node (ref "D8") (pin "C") (pinfunction "C_C") (pintype "passive"))
      (node (ref "U8") (pin "1") (pinfunction "A_1") (pintype "passive"))
    )
    (net (code "59") (name "Net-(U9-A)") (class "Default")
      (node (ref "D25") (pin "C") (pinfunction "C_C") (pintype "passive"))
      (node (ref "D9") (pin "C") (pinfunction "C_C") (pintype "passive"))
      (node (ref "U9") (pin "1") (pinfunction "A_1") (pintype "passive"))
    )
    (net (code "60") (name "Net-(U10-A)") (class "Default")
      (node (ref "D10") (pin "C") (pinfunction "C_C") (pintype "passive"))
      (node (ref "D26") (pin "C") (pinfunction "C_C") (pintype "passive"))
      (node (ref "U10") (pin "1") (pinfunction "A_1") (pintype "passive"))
    )
    (net (code "61") (name "Net-(U12-V3)") (class "Default")
      (node (ref "C8") (pin "1") (pinfunction "1_1") (pintype "passive"))
      (node (ref "U12") (pin "4") (pinfunction "V3_4") (pintype "power_in"))
    )
    (net (code "62") (name "Net-(U12-XI)") (class "Default")
      (node (ref "C1") (pin "2") (pinfunction "2_2") (pintype "passive"))
      (node (ref "Q1") (pin "2") (pinfunction "2_2") (pintype "passive"))
      (node (ref "U12") (pin "7") (pinfunction "XI_7") (pintype "input"))
    )
    (net (code "63") (name "Net-(U12-XO)") (class "Default")
      (node (ref "C2") (pin "2") (pinfunction "2_2") (pintype "passive"))
      (node (ref "Q1") (pin "1") (pinfunction "1_1") (pintype "passive"))
      (node (ref "U12") (pin "8") (pinfunction "XO_8") (pintype "output"))
    )
    (net (code "64") (name "Net-(X9B-1)") (class "Default")
      (node (ref "JP2") (pin "1") (pinfunction "1_1") (pintype "passive"))
      (node (ref "X9") (pin "2") (pinfunction "1_2") (pintype "passive"))
    )
    (net (code "65") (name "Net-(X9C-1)") (class "Default")
      (node (ref "JP2") (pin "3") (pinfunction "3_3") (pintype "passive"))
      (node (ref "X9") (pin "3") (pinfunction "1_3") (pintype "passive"))
    )
    (net (code "66") (name "OUT1") (class "Default")
      (node (ref "IC1") (pin "21") (pinfunction "GPA0_21") (pintype "bidirectional"))
      (node (ref "R17") (pin "2") (pinfunction "2_2") (pintype "passive"))
      (node (ref "U1") (pin "4") (pinfunction "CT_4") (pintype "passive"))
    )
    (net (code "67") (name "OUT2") (class "Default")
      (node (ref "IC1") (pin "22") (pinfunction "GPA1_22") (pintype "bidirectional"))
      (node (ref "R18") (pin "2") (pinfunction "2_2") (pintype "passive"))
      (node (ref "U2") (pin "4") (pinfunction "CT_4") (pintype "passive"))
    )
    (net (code "68") (name "OUT3") (class "Default")
      (node (ref "IC1") (pin "23") (pinfunction "GPA2_23") (pintype "bidirectional"))
      (node (ref "R19") (pin "2") (pinfunction "2_2") (pintype "passive"))
      (node (ref "U3") (pin "4") (pinfunction "CT_4") (pintype "passive"))
    )
    (net (code "69") (name "OUT4") (class "Default")
      (node (ref "IC1") (pin "24") (pinfunction "GPA3_24") (pintype "bidirectional"))
      (node (ref "R20") (pin "2") (pinfunction "2_2") (pintype "passive"))
      (node (ref "U4") (pin "4") (pinfunction "CT_4") (pintype "passive"))
    )
    (net (code "70") (name "OUT5") (class "Default")
      (node (ref "IC1") (pin "25") (pinfunction "GPA4_25") (pintype "bidirectional"))
      (node (ref "R21") (pin "2") (pinfunction "2_2") (pintype "passive"))
      (node (ref "U5") (pin "4") (pinfunction "CT_4") (pintype "passive"))
    )
    (net (code "71") (name "OUT6") (class "Default")
      (node (ref "IC1") (pin "26") (pinfunction "GPA5_26") (pintype "bidirectional"))
      (node (ref "R22") (pin "2") (pinfunction "2_2") (pintype "passive"))
      (node (ref "U6") (pin "4") (pinfunction "CT_4") (pintype "passive"))
    )
    (net (code "72") (name "OUT7") (class "Default")
      (node (ref "IC1") (pin "27") (pinfunction "GPA6_27") (pintype "bidirectional"))
      (node (ref "R23") (pin "2") (pinfunction "2_2") (pintype "passive"))
      (node (ref "U7") (pin "4") (pinfunction "CT_4") (pintype "passive"))
    )
    (net (code "73") (name "OUT8") (class "Default")
      (node (ref "IC1") (pin "28") (pinfunction "GPA7_28") (pintype "bidirectional"))
      (node (ref "R24") (pin "2") (pinfunction "2_2") (pintype "passive"))
      (node (ref "U8") (pin "4") (pinfunction "CT_4") (pintype "passive"))
    )
    (net (code "74") (name "OUT9") (class "Default")
      (node (ref "IC1") (pin "1") (pinfunction "GPB0_1") (pintype "bidirectional"))
      (node (ref "R25") (pin "2") (pinfunction "2_2") (pintype "passive"))
      (node (ref "U9") (pin "4") (pinfunction "CT_4") (pintype "passive"))
    )
    (net (code "75") (name "OUT10") (class "Default")
      (node (ref "IC1") (pin "2") (pinfunction "GPB1_2") (pintype "bidirectional"))
      (node (ref "R26") (pin "2") (pinfunction "2_2") (pintype "passive"))
      (node (ref "U10") (pin "4") (pinfunction "CT_4") (pintype "passive"))
    )
    (net (code "76") (name "P1") (class "Default")
      (node (ref "R1") (pin "1") (pinfunction "1_1") (pintype "passive"))
      (node (ref "X1") (pin "1") (pinfunction "1_1") (pintype "passive"))
    )
    (net (code "77") (name "P2") (class "Default")
      (node (ref "R2") (pin "1") (pinfunction "1_1") (pintype "passive"))
      (node (ref "X1") (pin "2") (pinfunction "1_2") (pintype "passive"))
    )
    (net (code "78") (name "P3") (class "Default")
      (node (ref "R3") (pin "1") (pinfunction "1_1") (pintype "passive"))
      (node (ref "X1") (pin "3") (pinfunction "1_3") (pintype "passive"))
    )
    (net (code "79") (name "P4") (class "Default")
      (node (ref "R4") (pin "1") (pinfunction "1_1") (pintype "passive"))
      (node (ref "X1") (pin "4") (pinfunction "1_4") (pintype "passive"))
    )
    (net (code "80") (name "P5") (class "Default")
      (node (ref "R5") (pin "1") (pinfunction "1_1") (pintype "passive"))
      (node (ref "X1") (pin "5") (pinfunction "1_5") (pintype "passive"))
    )
    (net (code "81") (name "P6") (class "Default")
      (node (ref "R6") (pin "1") (pinfunction "1_1") (pintype "passive"))
      (node (ref "X2") (pin "5") (pinfunction "1_5") (pintype "passive"))
    )
    (net (code "82") (name "P7") (class "Default")
      (node (ref "R7") (pin "1") (pinfunction "1_1") (pintype "passive"))
      (node (ref "X2") (pin "4") (pinfunction "1_4") (pintype "passive"))
    )
    (net (code "83") (name "P8") (class "Default")
      (node (ref "R8") (pin "1") (pinfunction "1_1") (pintype "passive"))
      (node (ref "X2") (pin "3") (pinfunction "1_3") (pintype "passive"))
    )
    (net (code "84") (name "P9") (class "Default")
      (node (ref "R9") (pin "1") (pinfunction "1_1") (pintype "passive"))
      (node (ref "X2") (pin "2") (pinfunction "1_2") (pintype "passive"))
    )
    (net (code "85") (name "P10") (class "Default")
      (node (ref "R10") (pin "1") (pinfunction "1_1") (pintype "passive"))
      (node (ref "X2") (pin "1") (pinfunction "1_1") (pintype "passive"))
    )
    (net (code "86") (name "RST_LORA") (class "Default")
      (node (ref "LORA-NICERF-V1") (pin "NRST") (pinfunction "NRST_NRST") (pintype "bidirectional"))
      (node (ref "U13") (pin "23") (pinfunction "IO15_23") (pintype "bidirectional"))
    )
    (net (code "87") (name "RTS") (class "Default")
      (node (ref "Q2") (pin "2") (pinfunction "E_2") (pintype "passive"))
      (node (ref "R30") (pin "2") (pinfunction "2_2") (pintype "passive"))
      (node (ref "U12") (pin "14") (pinfunction "~{RTS}_14") (pintype "output"))
    )
    (net (code "88") (name "RX") (class "Default")
      (node (ref "D15") (pin "C") (pinfunction "C_C") (pintype "passive"))
      (node (ref "U12") (pin "3") (pinfunction "RXD_3") (pintype "input"))
      (node (ref "U13") (pin "35") (pinfunction "TXD0_35") (pintype "bidirectional"))
    )
    (net (code "89") (name "RX_RS485") (class "Default")
      (node (ref "TTL-RS1") (pin "RX") (pinfunction "RX_RX") (pintype "bidirectional"))
      (node (ref "U13") (pin "28") (pinfunction "IO17_28") (pintype "bidirectional"))
    )
    (net (code "90") (name "SCK_HSPI") (class "Default")
      (node (ref "LORA-NICERF-V1") (pin "SCK") (pinfunction "SCK_SCK") (pintype "bidirectional"))
      (node (ref "U13") (pin "13") (pinfunction "IO14_13") (pintype "bidirectional"))
    )
    (net (code "91") (name "SCK_LAN") (class "Default")
      (node (ref "U$1") (pin "SCLK") (pinfunction "SCLK_SCLK") (pintype "bidirectional"))
      (node (ref "U13") (pin "30") (pinfunction "IO18_30") (pintype "bidirectional"))
    )
    (net (code "92") (name "SCL") (class "Default")
      (node (ref "IC1") (pin "12") (pinfunction "SCL_12") (pintype "input"))
      (node (ref "R11") (pin "2") (pinfunction "2_2") (pintype "passive"))
      (node (ref "U11") (pin "10") (pinfunction "SCL_10") (pintype "input"))
      (node (ref "U13") (pin "36") (pinfunction "IO22_36") (pintype "bidirectional"))
    )
    (net (code "93") (name "SDA") (class "Default")
      (node (ref "IC1") (pin "13") (pinfunction "SDA_13") (pintype "bidirectional"))
      (node (ref "R12") (pin "2") (pinfunction "2_2") (pintype "passive"))
      (node (ref "U11") (pin "9") (pinfunction "SDA_9") (pintype "bidirectional"))
      (node (ref "U13") (pin "33") (pinfunction "IO21_33") (pintype "bidirectional"))
    )
    (net (code "94") (name "SS_LAN") (class "Default")
      (node (ref "U$1") (pin "CS") (pinfunction "CS_CS") (pintype "bidirectional"))
      (node (ref "U13") (pin "29") (pinfunction "IO5_29") (pintype "bidirectional"))
    )
    (net (code "95") (name "SS_LORA") (class "Default")
      (node (ref "LORA-NICERF-V1") (pin "NSS") (pinfunction "NSS_NSS") (pintype "bidirectional"))
      (node (ref "U13") (pin "26") (pinfunction "IO4_26") (pintype "bidirectional"))
    )
    (net (code "96") (name "TX") (class "Default")
      (node (ref "D14") (pin "C") (pinfunction "C_C") (pintype "passive"))
      (node (ref "U12") (pin "2") (pinfunction "TXD_2") (pintype "output"))
      (node (ref "U13") (pin "34") (pinfunction "RXD0_34") (pintype "bidirectional"))
    )
    (net (code "97") (name "TX_RS485") (class "Default")
      (node (ref "TTL-RS1") (pin "TX") (pinfunction "TX_TX") (pintype "bidirectional"))
      (node (ref "U13") (pin "27") (pinfunction "IO16_27") (pintype "bidirectional"))
    )
    (net (code "98") (name "USB_N") (class "Default")
      (node (ref "J2") (pin "2") (pinfunction "D-_2") (pintype "passive"))
      (node (ref "U12") (pin "6") (pinfunction "UD-_6") (pintype "bidirectional"))
    )
    (net (code "99") (name "USB_P") (class "Default")
      (node (ref "J2") (pin "3") (pinfunction "D+_3") (pintype "passive"))
      (node (ref "U12") (pin "5") (pinfunction "UD+_5") (pintype "bidirectional"))
    )
    (net (code "100") (name "VCC") (class "Default")
      (node (ref "C10") (pin "2") (pinfunction "2_2") (pintype "passive"))
      (node (ref "C5") (pin "2") (pinfunction "2_2") (pintype "passive"))
      (node (ref "D11") (pin "C") (pinfunction "K_C") (pintype "passive"))
      (node (ref "D12") (pin "C") (pinfunction "K_C") (pintype "passive"))
      (node (ref "IC1") (pin "9") (pinfunction "VDD_9") (pintype "power_in"))
      (node (ref "PZEM-DC1") (pin "5V") (pinfunction "5V_5V") (pintype "bidirectional"))
      (node (ref "PZEM-DC1") (pin "VCC1") (pinfunction "VCC1_VCC1") (pintype "bidirectional"))
      (node (ref "PZEM-DC2") (pin "5V") (pinfunction "5V_5V") (pintype "bidirectional"))
      (node (ref "PZEM-DC2") (pin "VCC1") (pinfunction "VCC1_VCC1") (pintype "bidirectional"))
      (node (ref "R11") (pin "1") (pinfunction "1_1") (pintype "passive"))
      (node (ref "R12") (pin "1") (pinfunction "1_1") (pintype "passive"))
      (node (ref "R16") (pin "1") (pinfunction "1_1") (pintype "passive"))
      (node (ref "R17") (pin "1") (pinfunction "1_1") (pintype "passive"))
      (node (ref "R18") (pin "1") (pinfunction "1_1") (pintype "passive"))
      (node (ref "R19") (pin "1") (pinfunction "1_1") (pintype "passive"))
      (node (ref "R20") (pin "1") (pinfunction "1_1") (pintype "passive"))
      (node (ref "R21") (pin "1") (pinfunction "1_1") (pintype "passive"))
      (node (ref "R22") (pin "1") (pinfunction "1_1") (pintype "passive"))
      (node (ref "R23") (pin "1") (pinfunction "1_1") (pintype "passive"))
      (node (ref "R24") (pin "1") (pinfunction "1_1") (pintype "passive"))
      (node (ref "R25") (pin "1") (pinfunction "1_1") (pintype "passive"))
      (node (ref "R26") (pin "1") (pinfunction "1_1") (pintype "passive"))
      (node (ref "R33") (pin "2") (pinfunction "2_2") (pintype "passive"))
      (node (ref "TTL-RS1") (pin "VCC") (pinfunction "VCC_VCC") (pintype "bidirectional"))
      (node (ref "U$1") (pin "3V3") (pinfunction "3V3_3V3") (pintype "bidirectional"))
      (node (ref "U$1") (pin "3V3.2") (pinfunction "3V3.2_3V3.2") (pintype "bidirectional"))
      (node (ref "U11") (pin "8") (pinfunction "VDD_8") (pintype "power_in"))
      (node (ref "U14") (pin "3") (pinfunction "VIN_3") (pintype "input"))
      (node (ref "X4") (pin "1") (pinfunction "1_1") (pintype "passive"))
    )
    (net (code "101") (name "VOLT1+") (class "Default")
      (node (ref "PZEM-DC1") (pin "VDC+") (pinfunction "+VDC_VDC+") (pintype "bidirectional"))
      (node (ref "X7") (pin "1") (pinfunction "1_1") (pintype "passive"))
    )
    (net (code "102") (name "VOLT1-") (class "Default")
      (node (ref "PZEM-DC1") (pin "VDC-") (pinfunction "-VDC_VDC-") (pintype "bidirectional"))
      (node (ref "X7") (pin "2") (pinfunction "1_2") (pintype "passive"))
    )
    (net (code "103") (name "VOLT2+") (class "Default")
      (node (ref "PZEM-DC2") (pin "VDC+") (pinfunction "+VDC_VDC+") (pintype "bidirectional"))
      (node (ref "X8") (pin "1") (pinfunction "1_1") (pintype "passive"))
    )
    (net (code "104") (name "VOLT2-") (class "Default")
      (node (ref "PZEM-DC2") (pin "VDC-") (pinfunction "-VDC_VDC-") (pintype "bidirectional"))
      (node (ref "X8") (pin "2") (pinfunction "1_2") (pintype "passive"))
    )
    (net (code "105") (name "VUSB") (class "Default")
      (node (ref "C7") (pin "1") (pinfunction "1_1") (pintype "passive"))
      (node (ref "C9") (pin "+") (pinfunction "+_+") (pintype "passive"))
      (node (ref "D12") (pin "A") (pinfunction "A_A") (pintype "passive"))
      (node (ref "J2") (pin "1") (pinfunction "VUSB_1") (pintype "passive"))
      (node (ref "U12") (pin "16") (pinfunction "VCC_16") (pintype "power_in"))
    )
    (net (code "106") (name "unconnected-(IC1-GPB2-Pad3)") (class "Default")
      (node (ref "IC1") (pin "3") (pinfunction "GPB2_3") (pintype "bidirectional"))
    )
    (net (code "107") (name "unconnected-(IC1-GPB3-Pad4)") (class "Default")
      (node (ref "IC1") (pin "4") (pinfunction "GPB3_4") (pintype "bidirectional"))
    )
    (net (code "108") (name "unconnected-(IC1-GPB4-Pad5)") (class "Default")
      (node (ref "IC1") (pin "5") (pinfunction "GPB4_5") (pintype "bidirectional"))
    )
    (net (code "109") (name "unconnected-(IC1-GPB5-Pad6)") (class "Default")
      (node (ref "IC1") (pin "6") (pinfunction "GPB5_6") (pintype "bidirectional"))
    )
    (net (code "110") (name "unconnected-(IC1-GPB6-Pad7)") (class "Default")
      (node (ref "IC1") (pin "7") (pinfunction "GPB6_7") (pintype "bidirectional"))
    )
    (net (code "111") (name "unconnected-(IC1-GPB7-Pad8)") (class "Default")
      (node (ref "IC1") (pin "8") (pinfunction "GPB7_8") (pintype "bidirectional"))
    )
    (net (code "112") (name "unconnected-(IC1-INTA-Pad20)") (class "Default")
      (node (ref "IC1") (pin "20") (pinfunction "INTA_20") (pintype "output"))
    )
    (net (code "113") (name "unconnected-(IC1-INTB-Pad19)") (class "Default")
      (node (ref "IC1") (pin "19") (pinfunction "INTB_19") (pintype "output"))
    )
    (net (code "114") (name "unconnected-(J2-ID-Pad4)") (class "Default")
      (node (ref "J2") (pin "4") (pinfunction "ID_4") (pintype "passive"))
    )
    (net (code "115") (name "unconnected-(JP1-Pad2)") (class "Default")
      (node (ref "JP1") (pin "2") (pinfunction "2_2") (pintype "passive"))
    )
    (net (code "116") (name "unconnected-(JP2-Pad2)") (class "Default")
      (node (ref "JP2") (pin "2") (pinfunction "2_2") (pintype "passive"))
    )
    (net (code "117") (name "unconnected-(LORA-NICERF-V1-PadDIO2)") (class "Default")
      (node (ref "LORA-NICERF-V1") (pin "DIO2") (pinfunction "DIO2_DIO2") (pintype "bidirectional"))
    )
    (net (code "118") (name "unconnected-(LORA-NICERF-V1-PadNC)") (class "Default")
      (node (ref "LORA-NICERF-V1") (pin "NC") (pinfunction "NC_NC") (pintype "bidirectional"))
    )
    (net (code "119") (name "unconnected-(LORA-NICERF-V1-PadNC1)") (class "Default")
      (node (ref "LORA-NICERF-V1") (pin "NC1") (pinfunction "NC1_NC1") (pintype "bidirectional"))
    )
    (net (code "120") (name "unconnected-(PZEM-DC1-PadCT+)") (class "Default")
      (node (ref "PZEM-DC1") (pin "CT+") (pinfunction "CT+_CT+") (pintype "bidirectional"))
    )
    (net (code "121") (name "unconnected-(PZEM-DC1-PadCT-)") (class "Default")
      (node (ref "PZEM-DC1") (pin "CT-") (pinfunction "CT-_CT-") (pintype "bidirectional"))
    )
    (net (code "122") (name "unconnected-(PZEM-DC2-PadCT+)") (class "Default")
      (node (ref "PZEM-DC2") (pin "CT+") (pinfunction "CT+_CT+") (pintype "bidirectional"))
    )
    (net (code "123") (name "unconnected-(PZEM-DC2-PadCT-)") (class "Default")
      (node (ref "PZEM-DC2") (pin "CT-") (pinfunction "CT-_CT-") (pintype "bidirectional"))
    )
    (net (code "124") (name "unconnected-(U$1-PadINT)") (class "Default")
      (node (ref "U$1") (pin "INT") (pinfunction "INT_INT") (pintype "bidirectional"))
    )
    (net (code "125") (name "unconnected-(U$1-PadNC)") (class "Default")
      (node (ref "U$1") (pin "NC") (pinfunction "NC_NC") (pintype "bidirectional"))
    )
    (net (code "126") (name "unconnected-(U$1-PadRST)") (class "Default")
      (node (ref "U$1") (pin "RST") (pinfunction "RST_RST") (pintype "bidirectional"))
    )
    (net (code "127") (name "unconnected-(U11-AIN2-Pad6)") (class "Default")
      (node (ref "U11") (pin "6") (pinfunction "AIN2_6") (pintype "input"))
    )
    (net (code "128") (name "unconnected-(U11-AIN3-Pad7)") (class "Default")
      (node (ref "U11") (pin "7") (pinfunction "AIN3_7") (pintype "input"))
    )
    (net (code "129") (name "unconnected-(U11-ALERT{slash}RDY-Pad2)") (class "Default")
      (node (ref "U11") (pin "2") (pinfunction "ALERT/RDY_2") (pintype "output"))
    )
    (net (code "130") (name "unconnected-(U12-RS232-Pad15)") (class "Default")
      (node (ref "U12") (pin "15") (pinfunction "RS232_15") (pintype "input"))
    )
    (net (code "131") (name "unconnected-(U12-~{CTS}-Pad9)") (class "Default")
      (node (ref "U12") (pin "9") (pinfunction "~{CTS}_9") (pintype "input"))
    )
    (net (code "132") (name "unconnected-(U12-~{DCD}-Pad12)") (class "Default")
      (node (ref "U12") (pin "12") (pinfunction "~{DCD}_12") (pintype "input"))
    )
    (net (code "133") (name "unconnected-(U12-~{DSR}-Pad10)") (class "Default")
      (node (ref "U12") (pin "10") (pinfunction "~{DSR}_10") (pintype "input"))
    )
    (net (code "134") (name "unconnected-(U12-~{RI}-Pad11)") (class "Default")
      (node (ref "U12") (pin "11") (pinfunction "~{RI}_11") (pintype "input"))
    )
    (net (code "135") (name "unconnected-(U13-IO2-Pad24)") (class "Default")
      (node (ref "U13") (pin "24") (pinfunction "IO2_24") (pintype "bidirectional"))
    )
    (net (code "136") (name "unconnected-(U13-IO33-Pad9)") (class "Default")
      (node (ref "U13") (pin "9") (pinfunction "IO33_9") (pintype "bidirectional"))
    )
    (net (code "137") (name "unconnected-(U13-IO34-Pad6)") (class "Default")
      (node (ref "U13") (pin "6") (pinfunction "IO34_6") (pintype "input"))
    )
    (net (code "138") (name "unconnected-(U13-IO35-Pad7)") (class "Default")
      (node (ref "U13") (pin "7") (pinfunction "IO35_7") (pintype "input"))
    )
    (net (code "139") (name "unconnected-(U13-SCK{slash}CLK-Pad20)") (class "Default")
      (node (ref "U13") (pin "20") (pinfunction "SCK/CLK_20") (pintype "bidirectional"))
    )
    (net (code "140") (name "unconnected-(U13-SCS{slash}CMD-Pad19)") (class "Default")
      (node (ref "U13") (pin "19") (pinfunction "SCS/CMD_19") (pintype "bidirectional"))
    )
    (net (code "141") (name "unconnected-(U13-SDI{slash}SD1-Pad22)") (class "Default")
      (node (ref "U13") (pin "22") (pinfunction "SDI/SD1_22") (pintype "bidirectional"))
    )
    (net (code "142") (name "unconnected-(U13-SDO{slash}SD0-Pad21)") (class "Default")
      (node (ref "U13") (pin "21") (pinfunction "SDO/SD0_21") (pintype "bidirectional"))
    )
    (net (code "143") (name "unconnected-(U13-SENSOR_VN-Pad5)") (class "Default")
      (node (ref "U13") (pin "5") (pinfunction "SENSOR_VN_5") (pintype "input"))
    )
    (net (code "144") (name "unconnected-(U13-SENSOR_VP-Pad4)") (class "Default")
      (node (ref "U13") (pin "4") (pinfunction "SENSOR_VP_4") (pintype "input"))
    )
    (net (code "145") (name "unconnected-(U13-SHD{slash}SD2-Pad17)") (class "Default")
      (node (ref "U13") (pin "17") (pinfunction "SHD/SD2_17") (pintype "bidirectional"))
    )
    (net (code "146") (name "unconnected-(U13-SWP{slash}SD3-Pad18)") (class "Default")
      (node (ref "U13") (pin "18") (pinfunction "SWP/SD3_18") (pintype "bidirectional"))
    )
  )
)
